# PenguinPi_HAT.net
KiCad netlist of a schematic drawn in Altium Designer
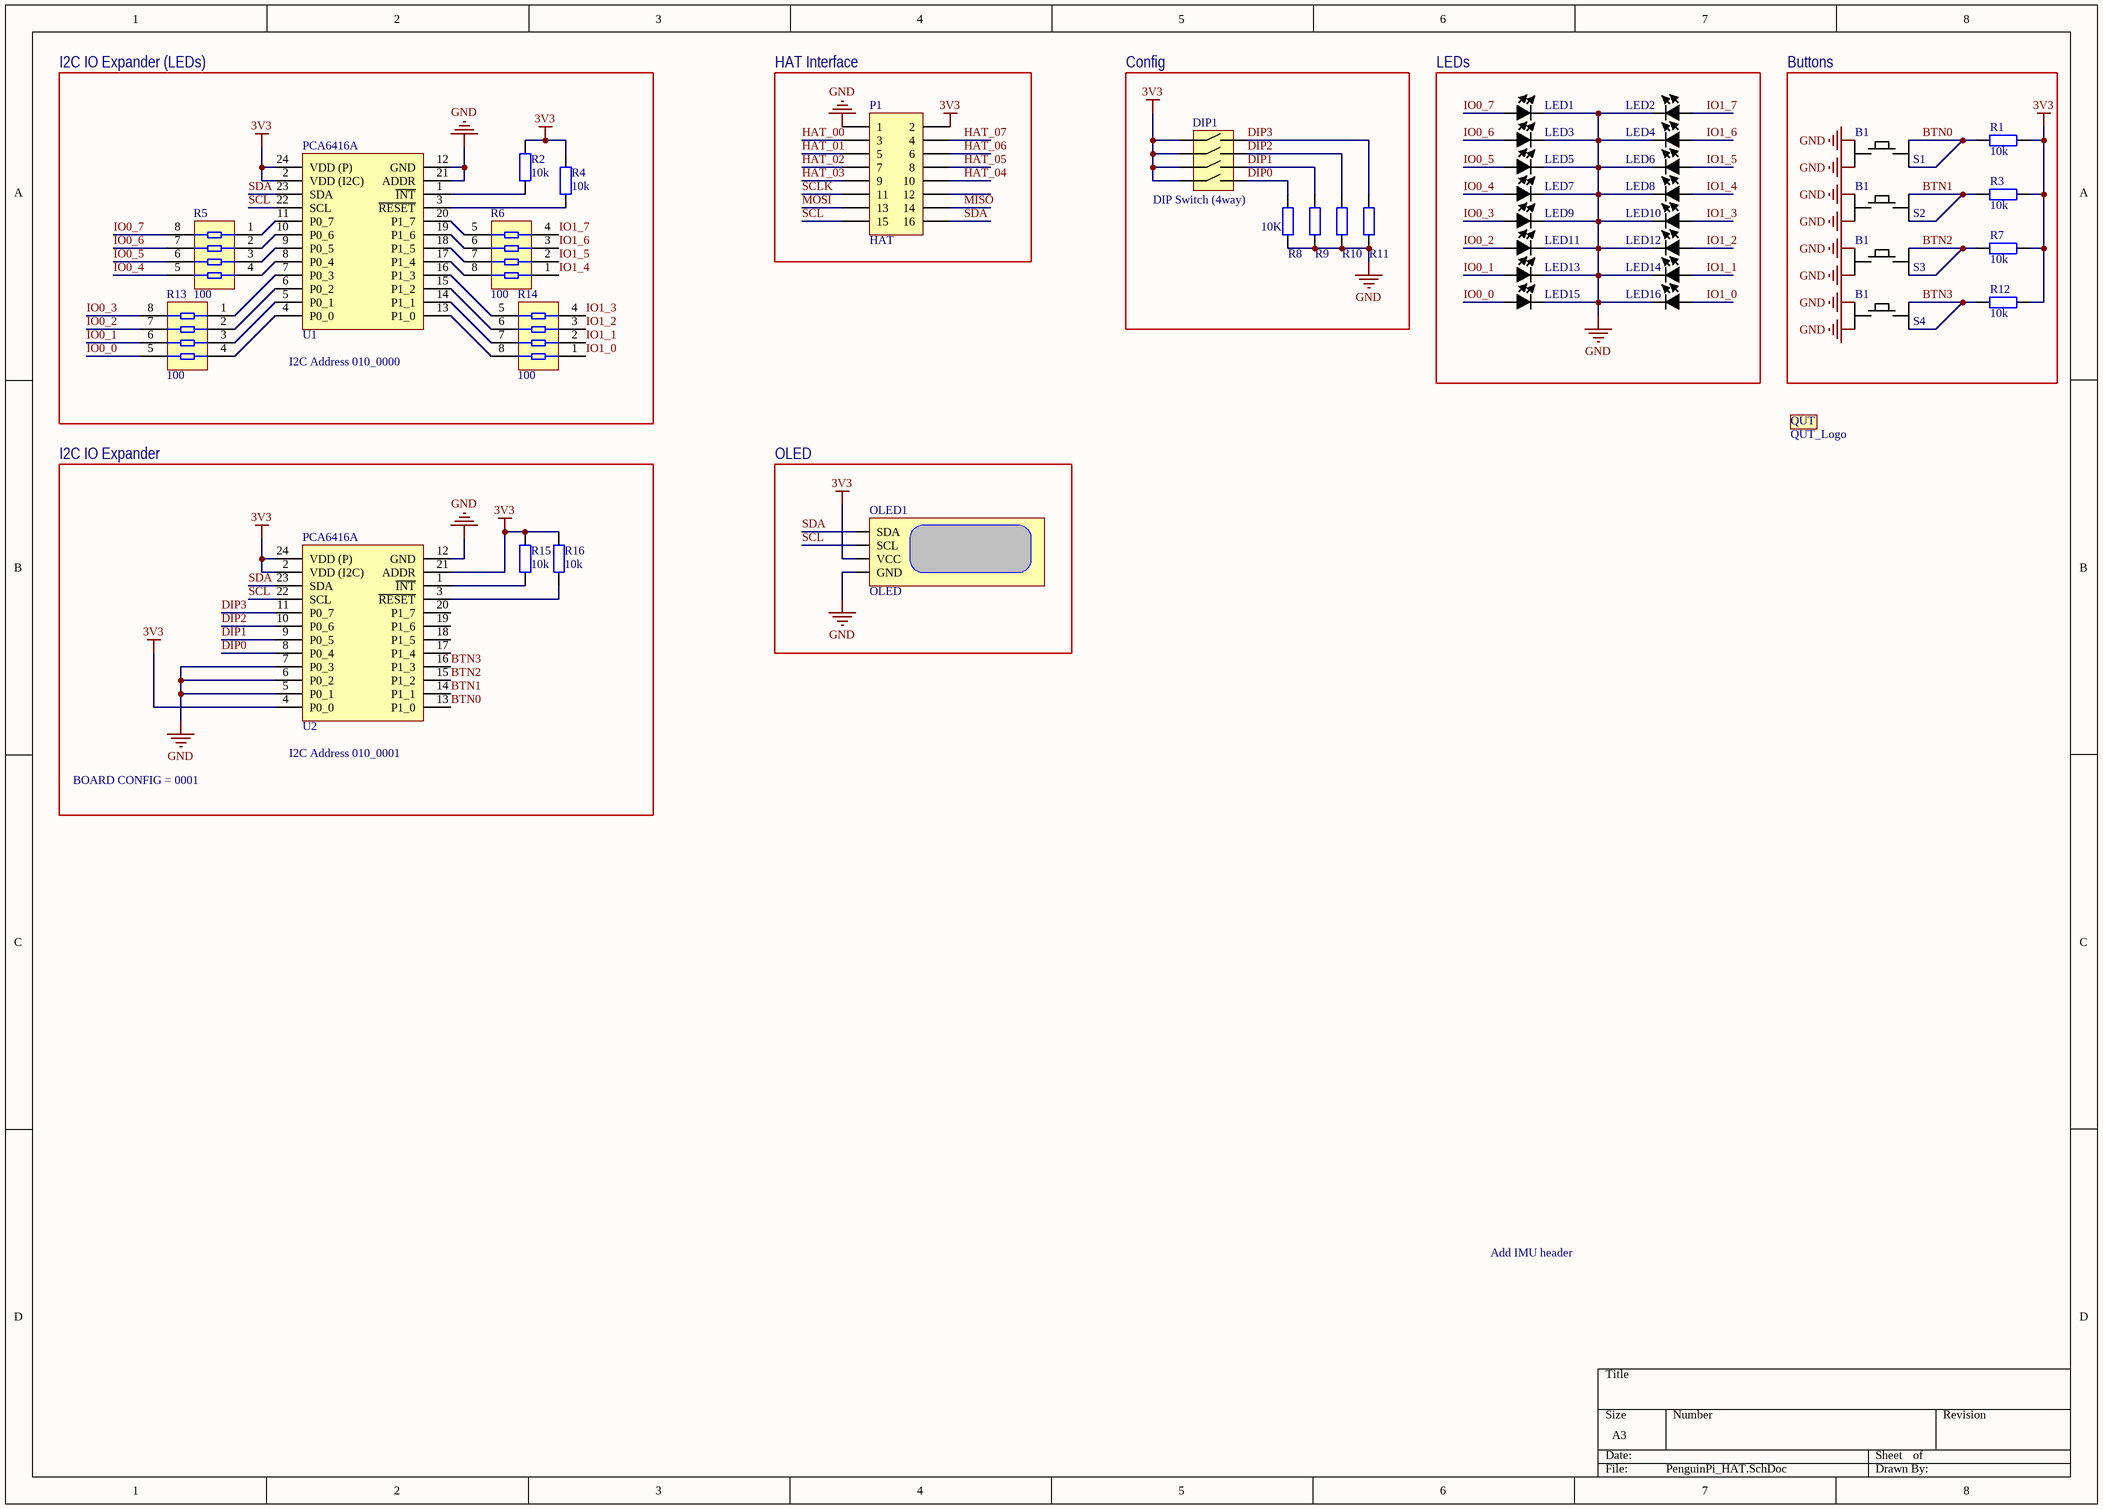
[diagram p0: PenguinPi_HAT.SchDoc]

(export (version "E")
  (design (tool "Eeschema 10.0.6"))
  (components
    (comp (ref "DIP1")
      (value "DIP Switch (4way)")
      (footprint "DIP SMD")
      (libsource (lib "QUT") (part "DIP Switch (4way)"))
    )
    (comp (ref "LED1") (value "LED*") (footprint "C0805") (libsource (lib "QUT") (part "LED")))
    (comp (ref "LED2") (value "LED*") (footprint "C0805") (libsource (lib "QUT") (part "LED")))
    (comp (ref "LED3") (value "LED*") (footprint "C0805") (libsource (lib "QUT") (part "LED")))
    (comp (ref "LED4") (value "LED*") (footprint "C0805") (libsource (lib "QUT") (part "LED")))
    (comp (ref "LED5") (value "LED*") (footprint "C0805") (libsource (lib "QUT") (part "LED")))
    (comp (ref "LED6") (value "LED*") (footprint "C0805") (libsource (lib "QUT") (part "LED")))
    (comp (ref "LED7") (value "LED*") (footprint "C0805") (libsource (lib "QUT") (part "LED")))
    (comp (ref "LED8") (value "LED*") (footprint "C0805") (libsource (lib "QUT") (part "LED")))
    (comp (ref "LED9") (value "LED*") (footprint "C0805") (libsource (lib "QUT") (part "LED")))
    (comp (ref "LED10") (value "LED*") (footprint "C0805") (libsource (lib "QUT") (part "LED")))
    (comp (ref "LED11") (value "LED*") (footprint "C0805") (libsource (lib "QUT") (part "LED")))
    (comp (ref "LED12") (value "LED*") (footprint "C0805") (libsource (lib "QUT") (part "LED")))
    (comp (ref "LED13") (value "LED*") (footprint "C0805") (libsource (lib "QUT") (part "LED")))
    (comp (ref "LED14") (value "LED*") (footprint "C0805") (libsource (lib "QUT") (part "LED")))
    (comp (ref "LED15") (value "LED*") (footprint "C0805") (libsource (lib "QUT") (part "LED")))
    (comp (ref "LED16") (value "LED*") (footprint "C0805") (libsource (lib "QUT") (part "LED")))
    (comp (ref "LG1") (value "QUT_Logo") (footprint "QUT_Logo") (libsource (lib "Penguin") (part "QUT_Logo")))
    (comp (ref "OLED1") (value "OLED") (footprint "OLED") (libsource (lib "PenguinPi_v2") (part "OLED")))
    (comp (ref "P1")
      (value "HAT")
      (footprint "HDR2X8")
      (description "Header, 8-Pin, Dual row")
      (fields (field (name "PUBLISHER") "Altium Limited"))
      (libsource (lib "Miscellaneous Connectors") (part "Header 8X2"))
    )
    (comp (ref "R1")
      (value "10k")
      (footprint "RESC2012X07N")
      (description "0805 surface mount resistor")
      (fields (field (name "Comment") "RES SMD"))
      (libsource (lib "") (part "RES SMD_1"))
    )
    (comp (ref "R2")
      (value "10k")
      (footprint "RESC2012X07N")
      (description "0805 surface mount resistor")
      (fields (field (name "Comment") "RES SMD"))
      (libsource (lib "Penguin") (part "RES SMD"))
    )
    (comp (ref "R3")
      (value "10k")
      (footprint "RESC2012X07N")
      (description "0805 surface mount resistor")
      (fields (field (name "Comment") "RES SMD"))
      (libsource (lib "") (part "RES SMD_1"))
    )
    (comp (ref "R4")
      (value "10k")
      (footprint "RESC2012X07N")
      (description "0805 surface mount resistor")
      (fields (field (name "Comment") "RES SMD"))
      (libsource (lib "Penguin") (part "RES SMD"))
    )
    (comp (ref "R5")
      (value "100")
      (footprint "CAC-80P319X155-8M")
      (description "Surface mount resistor array")
      (fields (field (name "Comment") "ARRAY"))
      (libsource (lib "Penguin") (part "RES-ARRAY"))
    )
    (comp (ref "R6")
      (value "100")
      (footprint "CAC-80P319X155-8M")
      (description "Surface mount resistor array")
      (fields (field (name "Comment") "ARRAY"))
      (libsource (lib "") (part "RES-ARRAY_1"))
    )
    (comp (ref "R7")
      (value "10k")
      (footprint "RESC2012X07N")
      (description "0805 surface mount resistor")
      (fields (field (name "Comment") "RES SMD"))
      (libsource (lib "") (part "RES SMD_1"))
    )
    (comp (ref "R8")
      (value "10K")
      (footprint "RESC2012X07N")
      (description "0805 surface mount resistor")
      (fields (field (name "Comment") "RES SMD"))
      (libsource (lib "Penguin") (part "RES SMD"))
    )
    (comp (ref "R9")
      (value "RES SMD")
      (footprint "RESC2012X07N")
      (description "0805 surface mount resistor")
      (libsource (lib "Penguin") (part "RES SMD"))
    )
    (comp (ref "R10")
      (value "RES SMD")
      (footprint "RESC2012X07N")
      (description "0805 surface mount resistor")
      (libsource (lib "Penguin") (part "RES SMD"))
    )
    (comp (ref "R11")
      (value "RES SMD")
      (footprint "RESC2012X07N")
      (description "0805 surface mount resistor")
      (libsource (lib "Penguin") (part "RES SMD"))
    )
    (comp (ref "R12")
      (value "10k")
      (footprint "RESC2012X07N")
      (description "0805 surface mount resistor")
      (fields (field (name "Comment") "RES SMD"))
      (libsource (lib "") (part "RES SMD_1"))
    )
    (comp (ref "R13")
      (value "100")
      (footprint "CAC-80P319X155-8M")
      (description "Surface mount resistor array")
      (fields (field (name "Comment") "ARRAY"))
      (libsource (lib "Penguin") (part "RES-ARRAY"))
    )
    (comp (ref "R14")
      (value "100")
      (footprint "CAC-80P319X155-8M")
      (description "Surface mount resistor array")
      (fields (field (name "Comment") "ARRAY"))
      (libsource (lib "") (part "RES-ARRAY_1"))
    )
    (comp (ref "R15")
      (value "10k")
      (footprint "RESC2012X07N")
      (description "0805 surface mount resistor")
      (fields (field (name "Comment") "RES SMD"))
      (libsource (lib "Penguin") (part "RES SMD"))
    )
    (comp (ref "R16")
      (value "10k")
      (footprint "RESC2012X07N")
      (description "0805 surface mount resistor")
      (fields (field (name "Comment") "RES SMD"))
      (libsource (lib "Penguin") (part "RES SMD"))
    )
    (comp (ref "S1")
      (value "B1")
      (footprint "E-SWITCH-TL3342")
      (description "TL 3342 surface mount pushbutton")
      (libsource (lib "Penguin") (part "E-SWITCH-PUSHBUTTON"))
    )
    (comp (ref "S2")
      (value "B1")
      (footprint "E-SWITCH-TL3342")
      (description "TL 3342 surface mount pushbutton")
      (libsource (lib "Penguin") (part "E-SWITCH-PUSHBUTTON"))
    )
    (comp (ref "S3")
      (value "B1")
      (footprint "E-SWITCH-TL3342")
      (description "TL 3342 surface mount pushbutton")
      (libsource (lib "Penguin") (part "E-SWITCH-PUSHBUTTON"))
    )
    (comp (ref "S4")
      (value "B1")
      (footprint "E-SWITCH-TL3342")
      (description "TL 3342 surface mount pushbutton")
      (libsource (lib "Penguin") (part "E-SWITCH-PUSHBUTTON"))
    )
    (comp (ref "U1")
      (value "PCA6416A")
      (footprint "TSOP65P640X110-24N")
      (description "Low-voltage translating 16-bit I2C I/O port expander")
      (libsource (lib "Penguin") (part "PCA6416APW"))
    )
    (comp (ref "U2")
      (value "PCA6416A")
      (footprint "TSOP65P640X110-24N")
      (description "Low-voltage translating 16-bit I2C I/O port expander")
      (libsource (lib "Penguin") (part "PCA6416APW"))
    )
  )
  (nets
    (net (code "1") (name "/BTN0") (class "Default")
      (node (ref "R1") (pin "2") (pinfunction "2_2") (pintype "passive"))
      (node (ref "S1") (pin "3") (pinfunction "B'_3") (pintype "passive"))
      (node (ref "S1") (pin "4") (pinfunction "B_4") (pintype "passive"))
      (node (ref "U2") (pin "13") (pinfunction "P1_0_13") (pintype "passive"))
    )
    (net (code "2") (name "/BTN1") (class "Default")
      (node (ref "R3") (pin "2") (pinfunction "2_2") (pintype "passive"))
      (node (ref "S2") (pin "3") (pinfunction "B'_3") (pintype "passive"))
      (node (ref "S2") (pin "4") (pinfunction "B_4") (pintype "passive"))
      (node (ref "U2") (pin "14") (pinfunction "P1_1_14") (pintype "passive"))
    )
    (net (code "3") (name "/BTN2") (class "Default")
      (node (ref "R7") (pin "2") (pinfunction "2_2") (pintype "passive"))
      (node (ref "S3") (pin "3") (pinfunction "B'_3") (pintype "passive"))
      (node (ref "S3") (pin "4") (pinfunction "B_4") (pintype "passive"))
      (node (ref "U2") (pin "15") (pinfunction "P1_2_15") (pintype "passive"))
    )
    (net (code "4") (name "/BTN3") (class "Default")
      (node (ref "R12") (pin "2") (pinfunction "2_2") (pintype "passive"))
      (node (ref "S4") (pin "3") (pinfunction "B'_3") (pintype "passive"))
      (node (ref "S4") (pin "4") (pinfunction "B_4") (pintype "passive"))
      (node (ref "U2") (pin "16") (pinfunction "P1_3_16") (pintype "passive"))
    )
    (net (code "5") (name "/DIP0") (class "Default")
      (node (ref "DIP1") (pin "4") (pinfunction "4_4") (pintype "passive"))
      (node (ref "R8") (pin "2") (pinfunction "2_2") (pintype "passive"))
      (node (ref "U2") (pin "8") (pinfunction "P0_4_8") (pintype "passive"))
    )
    (net (code "6") (name "/DIP1") (class "Default")
      (node (ref "DIP1") (pin "5") (pinfunction "5_5") (pintype "passive"))
      (node (ref "R9") (pin "2") (pinfunction "2_2") (pintype "passive"))
      (node (ref "U2") (pin "9") (pinfunction "P0_5_9") (pintype "passive"))
    )
    (net (code "7") (name "/DIP2") (class "Default")
      (node (ref "DIP1") (pin "6") (pinfunction "6_6") (pintype "passive"))
      (node (ref "R10") (pin "2") (pinfunction "2_2") (pintype "passive"))
      (node (ref "U2") (pin "10") (pinfunction "P0_6_10") (pintype "passive"))
    )
    (net (code "8") (name "/DIP3") (class "Default")
      (node (ref "DIP1") (pin "7") (pinfunction "7_7") (pintype "passive"))
      (node (ref "R11") (pin "2") (pinfunction "2_2") (pintype "passive"))
      (node (ref "U2") (pin "11") (pinfunction "P0_7_11") (pintype "passive"))
    )
    (net (code "9") (name "/HAT_00") (class "Default")
      (node (ref "P1") (pin "3") (pinfunction "3_3") (pintype "passive"))
    )
    (net (code "10") (name "/HAT_01") (class "Default")
      (node (ref "P1") (pin "5") (pinfunction "5_5") (pintype "passive"))
    )
    (net (code "11") (name "/HAT_02") (class "Default")
      (node (ref "P1") (pin "7") (pinfunction "7_7") (pintype "passive"))
    )
    (net (code "12") (name "/HAT_03") (class "Default")
      (node (ref "P1") (pin "9") (pinfunction "9_9") (pintype "passive"))
    )
    (net (code "13") (name "/HAT_04") (class "Default")
      (node (ref "P1") (pin "10") (pinfunction "10_10") (pintype "passive"))
    )
    (net (code "14") (name "/HAT_05") (class "Default")
      (node (ref "P1") (pin "8") (pinfunction "8_8") (pintype "passive"))
    )
    (net (code "15") (name "/HAT_06") (class "Default")
      (node (ref "P1") (pin "6") (pinfunction "6_6") (pintype "passive"))
    )
    (net (code "16") (name "/HAT_07") (class "Default")
      (node (ref "P1") (pin "4") (pinfunction "4_4") (pintype "passive"))
    )
    (net (code "17") (name "/IO0_0") (class "Default")
      (node (ref "LED15") (pin "1") (pinfunction "1_1") (pintype "passive"))
      (node (ref "R13") (pin "5") (pintype "passive"))
    )
    (net (code "18") (name "/IO0_1") (class "Default")
      (node (ref "LED13") (pin "1") (pinfunction "1_1") (pintype "passive"))
      (node (ref "R13") (pin "6") (pintype "passive"))
    )
    (net (code "19") (name "/IO0_2") (class "Default")
      (node (ref "LED11") (pin "1") (pinfunction "1_1") (pintype "passive"))
      (node (ref "R13") (pin "7") (pintype "passive"))
    )
    (net (code "20") (name "/IO0_3") (class "Default")
      (node (ref "LED9") (pin "1") (pinfunction "1_1") (pintype "passive"))
      (node (ref "R13") (pin "8") (pintype "passive"))
    )
    (net (code "21") (name "/IO0_4") (class "Default")
      (node (ref "LED7") (pin "1") (pinfunction "1_1") (pintype "passive"))
      (node (ref "R5") (pin "5") (pintype "passive"))
    )
    (net (code "22") (name "/IO0_5") (class "Default")
      (node (ref "LED5") (pin "1") (pinfunction "1_1") (pintype "passive"))
      (node (ref "R5") (pin "6") (pintype "passive"))
    )
    (net (code "23") (name "/IO0_6") (class "Default")
      (node (ref "LED3") (pin "1") (pinfunction "1_1") (pintype "passive"))
      (node (ref "R5") (pin "7") (pintype "passive"))
    )
    (net (code "24") (name "/IO0_7") (class "Default")
      (node (ref "LED1") (pin "1") (pinfunction "1_1") (pintype "passive"))
      (node (ref "R5") (pin "8") (pintype "passive"))
    )
    (net (code "25") (name "/IO1_0") (class "Default")
      (node (ref "LED16") (pin "1") (pinfunction "1_1") (pintype "passive"))
      (node (ref "R14") (pin "1") (pintype "passive"))
    )
    (net (code "26") (name "/IO1_1") (class "Default")
      (node (ref "LED14") (pin "1") (pinfunction "1_1") (pintype "passive"))
      (node (ref "R14") (pin "2") (pintype "passive"))
    )
    (net (code "27") (name "/IO1_2") (class "Default")
      (node (ref "LED12") (pin "1") (pinfunction "1_1") (pintype "passive"))
      (node (ref "R14") (pin "3") (pintype "passive"))
    )
    (net (code "28") (name "/IO1_3") (class "Default")
      (node (ref "LED10") (pin "1") (pinfunction "1_1") (pintype "passive"))
      (node (ref "R14") (pin "4") (pintype "passive"))
    )
    (net (code "29") (name "/IO1_4") (class "Default")
      (node (ref "LED8") (pin "1") (pinfunction "1_1") (pintype "passive"))
      (node (ref "R6") (pin "1") (pintype "passive"))
    )
    (net (code "30") (name "/IO1_5") (class "Default")
      (node (ref "LED6") (pin "1") (pinfunction "1_1") (pintype "passive"))
      (node (ref "R6") (pin "2") (pintype "passive"))
    )
    (net (code "31") (name "/IO1_6") (class "Default")
      (node (ref "LED4") (pin "1") (pinfunction "1_1") (pintype "passive"))
      (node (ref "R6") (pin "3") (pintype "passive"))
    )
    (net (code "32") (name "/IO1_7") (class "Default")
      (node (ref "LED2") (pin "1") (pinfunction "1_1") (pintype "passive"))
      (node (ref "R6") (pin "4") (pintype "passive"))
    )
    (net (code "33") (name "/MISO") (class "Default")
      (node (ref "P1") (pin "14") (pinfunction "14_14") (pintype "passive"))
    )
    (net (code "34") (name "/MOSI") (class "Default")
      (node (ref "P1") (pin "13") (pinfunction "13_13") (pintype "passive"))
    )
    (net (code "35") (name "/SCL") (class "Default")
      (node (ref "OLED1") (pin "3") (pinfunction "SCL_3") (pintype "passive"))
      (node (ref "P1") (pin "15") (pinfunction "15_15") (pintype "passive"))
      (node (ref "U1") (pin "22") (pinfunction "SCL_22") (pintype "passive"))
      (node (ref "U2") (pin "22") (pinfunction "SCL_22") (pintype "passive"))
    )
    (net (code "36") (name "/SCLK") (class "Default")
      (node (ref "P1") (pin "11") (pinfunction "11_11") (pintype "passive"))
    )
    (net (code "37") (name "/SDA") (class "Default")
      (node (ref "OLED1") (pin "4") (pinfunction "SDA_4") (pintype "passive"))
      (node (ref "P1") (pin "16") (pinfunction "16_16") (pintype "passive"))
      (node (ref "U1") (pin "23") (pinfunction "SDA_23") (pintype "passive"))
      (node (ref "U2") (pin "23") (pinfunction "SDA_23") (pintype "passive"))
    )
    (net (code "38") (name "3V3") (class "Default")
      (node (ref "DIP1") (pin "0") (pinfunction "0_0") (pintype "passive"))
      (node (ref "DIP1") (pin "1") (pinfunction "1_1") (pintype "passive"))
      (node (ref "DIP1") (pin "2") (pinfunction "2_2") (pintype "passive"))
      (node (ref "DIP1") (pin "3") (pinfunction "3_3") (pintype "passive"))
      (node (ref "OLED1") (pin "2") (pinfunction "VCC_2") (pintype "passive"))
      (node (ref "P1") (pin "2") (pinfunction "2_2") (pintype "passive"))
      (node (ref "R1") (pin "1") (pinfunction "1_1") (pintype "passive"))
      (node (ref "R12") (pin "1") (pinfunction "1_1") (pintype "passive"))
      (node (ref "R15") (pin "2") (pinfunction "2_2") (pintype "passive"))
      (node (ref "R16") (pin "2") (pinfunction "2_2") (pintype "passive"))
      (node (ref "R2") (pin "2") (pinfunction "2_2") (pintype "passive"))
      (node (ref "R3") (pin "1") (pinfunction "1_1") (pintype "passive"))
      (node (ref "R4") (pin "2") (pinfunction "2_2") (pintype "passive"))
      (node (ref "R7") (pin "1") (pinfunction "1_1") (pintype "passive"))
      (node (ref "U1") (pin "2") (pinfunction "VDD_(I2C)_2") (pintype "passive"))
      (node (ref "U1") (pin "24") (pinfunction "VDD_(P)_24") (pintype "passive"))
      (node (ref "U2") (pin "2") (pinfunction "VDD_(I2C)_2") (pintype "passive"))
      (node (ref "U2") (pin "21") (pinfunction "ADDR_21") (pintype "passive"))
      (node (ref "U2") (pin "24") (pinfunction "VDD_(P)_24") (pintype "passive"))
      (node (ref "U2") (pin "4") (pinfunction "P0_0_4") (pintype "passive"))
    )
    (net (code "39") (name "GND") (class "Default")
      (node (ref "LED1") (pin "2") (pinfunction "2_2") (pintype "passive"))
      (node (ref "LED10") (pin "2") (pinfunction "2_2") (pintype "passive"))
      (node (ref "LED11") (pin "2") (pinfunction "2_2") (pintype "passive"))
      (node (ref "LED12") (pin "2") (pinfunction "2_2") (pintype "passive"))
      (node (ref "LED13") (pin "2") (pinfunction "2_2") (pintype "passive"))
      (node (ref "LED14") (pin "2") (pinfunction "2_2") (pintype "passive"))
      (node (ref "LED15") (pin "2") (pinfunction "2_2") (pintype "passive"))
      (node (ref "LED16") (pin "2") (pinfunction "2_2") (pintype "passive"))
      (node (ref "LED2") (pin "2") (pinfunction "2_2") (pintype "passive"))
      (node (ref "LED3") (pin "2") (pinfunction "2_2") (pintype "passive"))
      (node (ref "LED4") (pin "2") (pinfunction "2_2") (pintype "passive"))
      (node (ref "LED5") (pin "2") (pinfunction "2_2") (pintype "passive"))
      (node (ref "LED6") (pin "2") (pinfunction "2_2") (pintype "passive"))
      (node (ref "LED7") (pin "2") (pinfunction "2_2") (pintype "passive"))
      (node (ref "LED8") (pin "2") (pinfunction "2_2") (pintype "passive"))
      (node (ref "LED9") (pin "2") (pinfunction "2_2") (pintype "passive"))
      (node (ref "OLED1") (pin "1") (pinfunction "GND_1") (pintype "passive"))
      (node (ref "P1") (pin "1") (pinfunction "1_1") (pintype "passive"))
      (node (ref "R10") (pin "1") (pinfunction "1_1") (pintype "passive"))
      (node (ref "R11") (pin "1") (pinfunction "1_1") (pintype "passive"))
      (node (ref "R8") (pin "1") (pinfunction "1_1") (pintype "passive"))
      (node (ref "R9") (pin "1") (pinfunction "1_1") (pintype "passive"))
      (node (ref "S1") (pin "1") (pinfunction "A_1") (pintype "passive"))
      (node (ref "S1") (pin "2") (pinfunction "A'_2") (pintype "passive"))
      (node (ref "S2") (pin "1") (pinfunction "A_1") (pintype "passive"))
      (node (ref "S2") (pin "2") (pinfunction "A'_2") (pintype "passive"))
      (node (ref "S3") (pin "1") (pinfunction "A_1") (pintype "passive"))
      (node (ref "S3") (pin "2") (pinfunction "A'_2") (pintype "passive"))
      (node (ref "S4") (pin "1") (pinfunction "A_1") (pintype "passive"))
      (node (ref "S4") (pin "2") (pinfunction "A'_2") (pintype "passive"))
      (node (ref "U1") (pin "12") (pinfunction "GND_12") (pintype "passive"))
      (node (ref "U1") (pin "21") (pinfunction "ADDR_21") (pintype "passive"))
      (node (ref "U2") (pin "12") (pinfunction "GND_12") (pintype "passive"))
      (node (ref "U2") (pin "5") (pinfunction "P0_1_5") (pintype "passive"))
      (node (ref "U2") (pin "6") (pinfunction "P0_2_6") (pintype "passive"))
      (node (ref "U2") (pin "7") (pinfunction "P0_3_7") (pintype "passive"))
    )
    (net (code "40") (name "Net-(U1-P0_0)") (class "Default")
      (node (ref "R13") (pin "4") (pintype "passive"))
      (node (ref "U1") (pin "4") (pinfunction "P0_0_4") (pintype "passive"))
    )
    (net (code "41") (name "Net-(U1-P0_1)") (class "Default")
      (node (ref "R13") (pin "3") (pintype "passive"))
      (node (ref "U1") (pin "5") (pinfunction "P0_1_5") (pintype "passive"))
    )
    (net (code "42") (name "Net-(U1-P0_2)") (class "Default")
      (node (ref "R13") (pin "2") (pintype "passive"))
      (node (ref "U1") (pin "6") (pinfunction "P0_2_6") (pintype "passive"))
    )
    (net (code "43") (name "Net-(U1-P0_3)") (class "Default")
      (node (ref "R13") (pin "1") (pintype "passive"))
      (node (ref "U1") (pin "7") (pinfunction "P0_3_7") (pintype "passive"))
    )
    (net (code "44") (name "Net-(U1-P0_4)") (class "Default")
      (node (ref "R5") (pin "4") (pintype "passive"))
      (node (ref "U1") (pin "8") (pinfunction "P0_4_8") (pintype "passive"))
    )
    (net (code "45") (name "Net-(U1-P0_5)") (class "Default")
      (node (ref "R5") (pin "3") (pintype "passive"))
      (node (ref "U1") (pin "9") (pinfunction "P0_5_9") (pintype "passive"))
    )
    (net (code "46") (name "Net-(U1-P0_6)") (class "Default")
      (node (ref "R5") (pin "2") (pintype "passive"))
      (node (ref "U1") (pin "10") (pinfunction "P0_6_10") (pintype "passive"))
    )
    (net (code "47") (name "Net-(U1-P0_7)") (class "Default")
      (node (ref "R5") (pin "1") (pintype "passive"))
      (node (ref "U1") (pin "11") (pinfunction "P0_7_11") (pintype "passive"))
    )
    (net (code "48") (name "Net-(U1-P1_0)") (class "Default")
      (node (ref "R14") (pin "8") (pintype "passive"))
      (node (ref "U1") (pin "13") (pinfunction "P1_0_13") (pintype "passive"))
    )
    (net (code "49") (name "Net-(U1-P1_1)") (class "Default")
      (node (ref "R14") (pin "7") (pintype "passive"))
      (node (ref "U1") (pin "14") (pinfunction "P1_1_14") (pintype "passive"))
    )
    (net (code "50") (name "Net-(U1-P1_2)") (class "Default")
      (node (ref "R14") (pin "6") (pintype "passive"))
      (node (ref "U1") (pin "15") (pinfunction "P1_2_15") (pintype "passive"))
    )
    (net (code "51") (name "Net-(U1-P1_3)") (class "Default")
      (node (ref "R14") (pin "5") (pintype "passive"))
      (node (ref "U1") (pin "16") (pinfunction "P1_3_16") (pintype "passive"))
    )
    (net (code "52") (name "Net-(U1-P1_4)") (class "Default")
      (node (ref "R6") (pin "8") (pintype "passive"))
      (node (ref "U1") (pin "17") (pinfunction "P1_4_17") (pintype "passive"))
    )
    (net (code "53") (name "Net-(U1-P1_5)") (class "Default")
      (node (ref "R6") (pin "7") (pintype "passive"))
      (node (ref "U1") (pin "18") (pinfunction "P1_5_18") (pintype "passive"))
    )
    (net (code "54") (name "Net-(U1-P1_6)") (class "Default")
      (node (ref "R6") (pin "6") (pintype "passive"))
      (node (ref "U1") (pin "19") (pinfunction "P1_6_19") (pintype "passive"))
    )
    (net (code "55") (name "Net-(U1-P1_7)") (class "Default")
      (node (ref "R6") (pin "5") (pintype "passive"))
      (node (ref "U1") (pin "20") (pinfunction "P1_7_20") (pintype "passive"))
    )
    (net (code "56") (name "Net-(U1-~{INT})") (class "Default")
      (node (ref "R2") (pin "1") (pinfunction "1_1") (pintype "passive"))
      (node (ref "U1") (pin "1") (pinfunction "~{INT}_1") (pintype "passive"))
    )
    (net (code "57") (name "Net-(U1-~{RESET})") (class "Default")
      (node (ref "R4") (pin "1") (pinfunction "1_1") (pintype "passive"))
      (node (ref "U1") (pin "3") (pinfunction "~{RESET}_3") (pintype "passive"))
    )
    (net (code "58") (name "Net-(U2-~{INT})") (class "Default")
      (node (ref "R15") (pin "1") (pinfunction "1_1") (pintype "passive"))
      (node (ref "U2") (pin "1") (pinfunction "~{INT}_1") (pintype "passive"))
    )
    (net (code "59") (name "Net-(U2-~{RESET})") (class "Default")
      (node (ref "R16") (pin "1") (pinfunction "1_1") (pintype "passive"))
      (node (ref "U2") (pin "3") (pinfunction "~{RESET}_3") (pintype "passive"))
    )
    (net (code "60") (name "unconnected-(P1-Pad12)") (class "Default")
      (node (ref "P1") (pin "12") (pinfunction "12_12") (pintype "passive"))
    )
    (net (code "61") (name "unconnected-(U2-P1_4-Pad17)") (class "Default")
      (node (ref "U2") (pin "17") (pinfunction "P1_4_17") (pintype "passive"))
    )
    (net (code "62") (name "unconnected-(U2-P1_5-Pad18)") (class "Default")
      (node (ref "U2") (pin "18") (pinfunction "P1_5_18") (pintype "passive"))
    )
    (net (code "63") (name "unconnected-(U2-P1_6-Pad19)") (class "Default")
      (node (ref "U2") (pin "19") (pinfunction "P1_6_19") (pintype "passive"))
    )
    (net (code "64") (name "unconnected-(U2-P1_7-Pad20)") (class "Default")
      (node (ref "U2") (pin "20") (pinfunction "P1_7_20") (pintype "passive"))
    )
  )
)
